# MLX90393_Magnetometer_Breakout.net
KiCad netlist of a schematic drawn in EAGLE
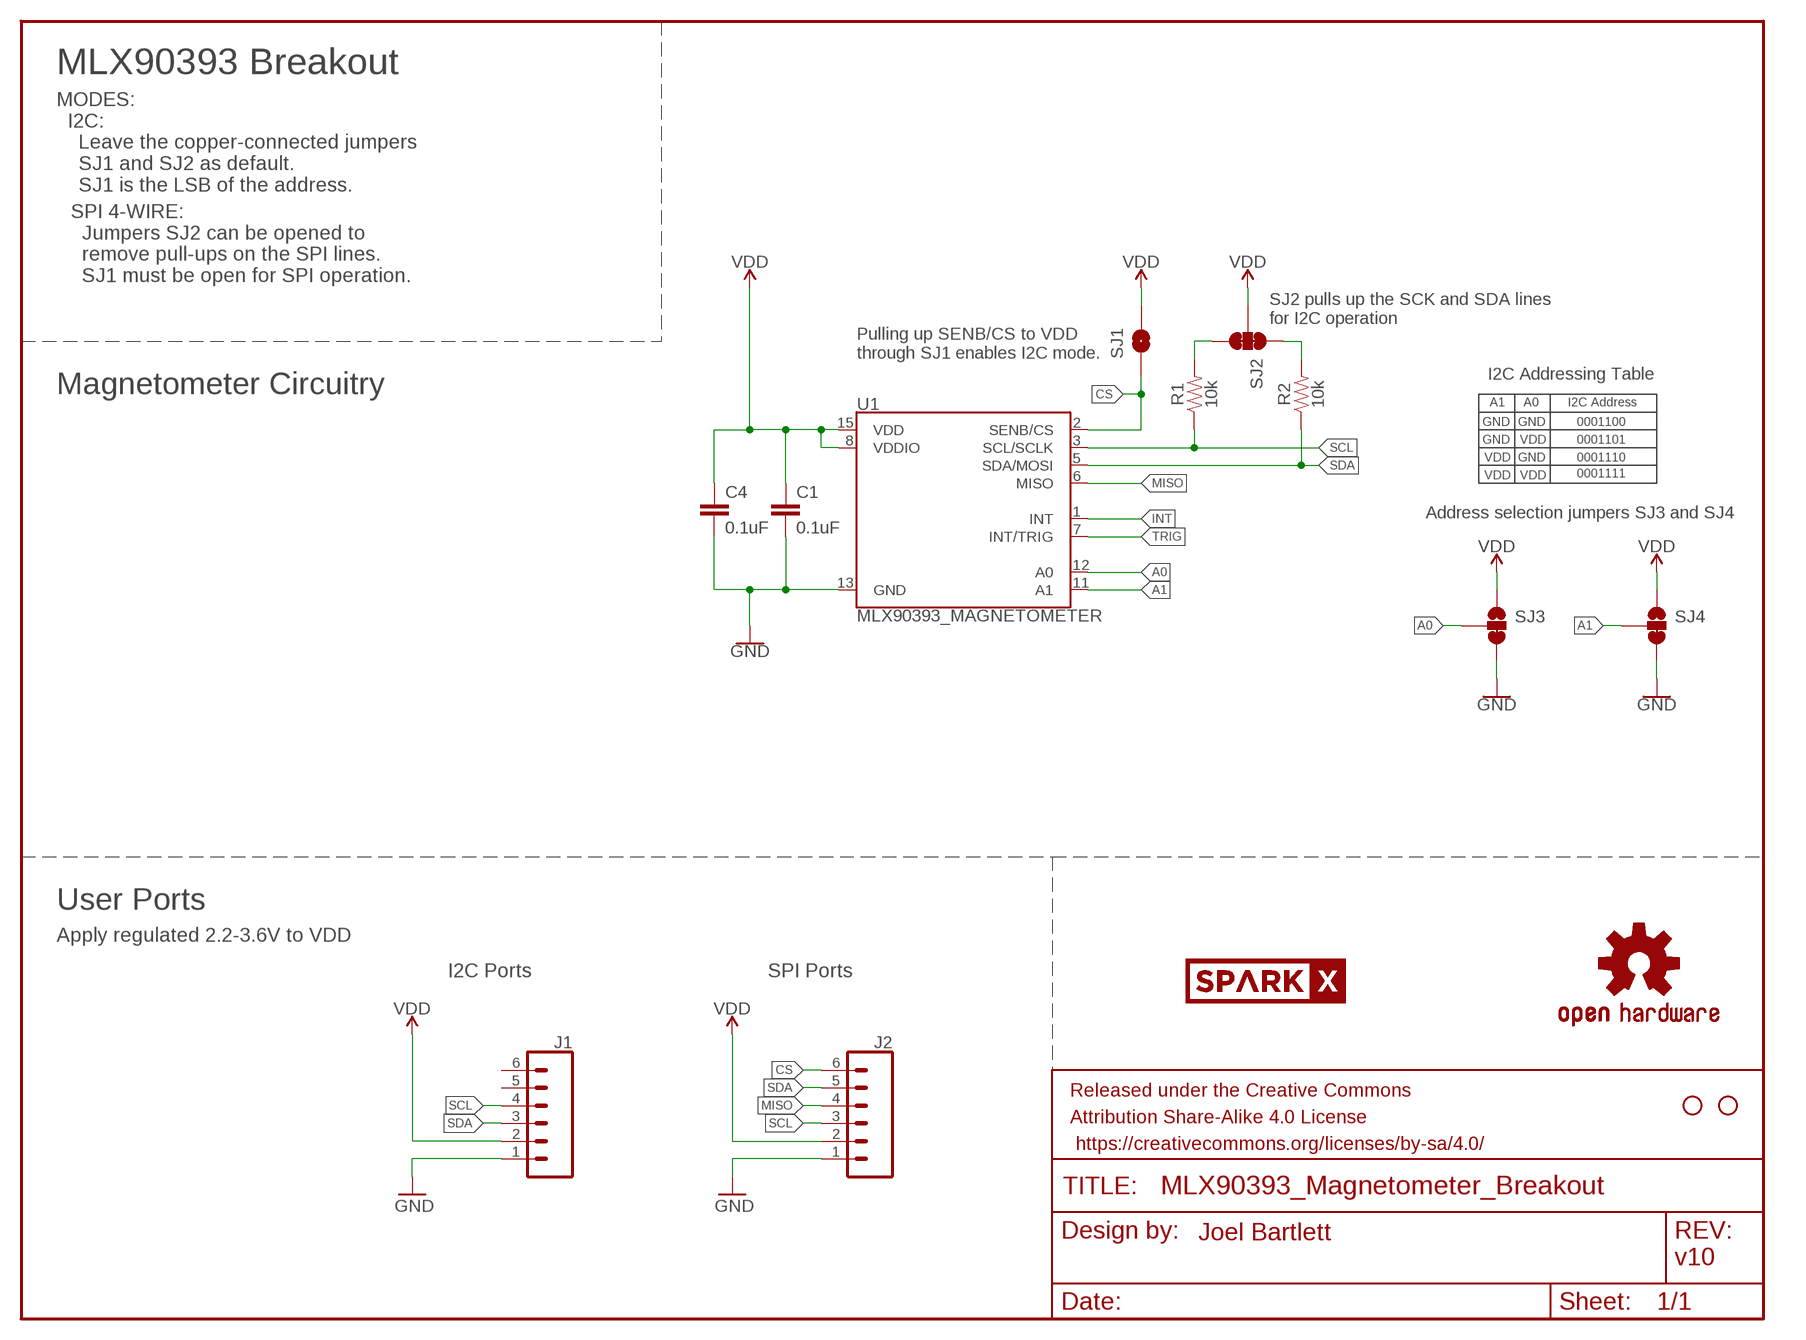
[diagram p0: schematic, sheet 1]

(export (version "E")
  (design (tool "Eeschema 10.0.6"))
  (components
    (comp (ref "C1")
      (value "0.1uF")
      (footprint "eagle-import:0603")
      (libsource (lib "eagle-import") (part "0.1UF-0603-25V-(+80/-20%)"))
    )
    (comp (ref "C4")
      (value "0.1uF")
      (footprint "eagle-import:0603")
      (libsource (lib "eagle-import") (part "0.1UF-0603-25V-(+80/-20%)"))
    )
    (comp (ref "FRAME2")
      (value "FRAME-LETTER")
      (footprint "eagle-import:CREATIVE_COMMONS")
      (libsource (lib "eagle-import") (part "FRAME-LETTER"))
    )
    (comp (ref "J1")
      (value "CONN_06NO_SILK_FEMALE_PTH")
      (footprint "eagle-import:1X06_NO_SILK")
      (libsource (lib "eagle-import") (part "CONN_06NO_SILK_FEMALE_PTH"))
    )
    (comp (ref "J2")
      (value "CONN_06NO_SILK_FEMALE_PTH")
      (footprint "eagle-import:1X06_NO_SILK")
      (libsource (lib "eagle-import") (part "CONN_06NO_SILK_FEMALE_PTH"))
    )
    (comp (ref "JP3")
      (value "STAND-OFF")
      (footprint "eagle-import:STAND-OFF")
      (libsource (lib "eagle-import") (part "STAND-OFF"))
    )
    (comp (ref "JP4")
      (value "STAND-OFF")
      (footprint "eagle-import:STAND-OFF")
      (libsource (lib "eagle-import") (part "STAND-OFF"))
    )
    (comp (ref "R1")
      (value "10k")
      (footprint "eagle-import:0603")
      (libsource (lib "eagle-import") (part "10KOHM-0603-1/10W-1%"))
    )
    (comp (ref "R2")
      (value "10k")
      (footprint "eagle-import:0603")
      (libsource (lib "eagle-import") (part "10KOHM-0603-1/10W-1%"))
    )
    (comp (ref "SJ1")
      (value "SOLDERJUMPERTRACE")
      (footprint "eagle-import:SJ_2S-TRACE")
      (libsource (lib "eagle-import") (part "SOLDERJUMPERTRACE"))
    )
    (comp (ref "SJ2")
      (value "JUMPER-PAD-3-NC_BY_TRACE")
      (footprint "eagle-import:PAD-JUMPER-3-3OF3_NC_BY_TRACE_YES_SILK_FULL_BOX")
      (libsource (lib "eagle-import") (part "JUMPER-PAD-3-NC_BY_TRACE"))
    )
    (comp (ref "SJ3")
      (value "JUMPER-SMT_3_1-NC_TRACE_SILK")
      (footprint "eagle-import:SMT-JUMPER_3_1-NC_TRACE_SILK")
      (libsource (lib "eagle-import") (part "JUMPER-SMT_3_1-NC_TRACE_SILK"))
    )
    (comp (ref "SJ4")
      (value "JUMPER-SMT_3_1-NC_TRACE_SILK")
      (footprint "eagle-import:SMT-JUMPER_3_1-NC_TRACE_SILK")
      (libsource (lib "eagle-import") (part "JUMPER-SMT_3_1-NC_TRACE_SILK"))
    )
    (comp (ref "U$1")
      (value "OSHW-LOGOS")
      (footprint "eagle-import:OSHW-LOGO-S")
      (libsource (lib "eagle-import") (part "OSHW-LOGOS"))
    )
    (comp (ref "U$2")
      (value "SPARKX-LOGO2")
      (footprint "eagle-import:SPARKX-TINY")
      (libsource (lib "eagle-import") (part "SPARKX-LOGO2"))
    )
    (comp (ref "U1")
      (value "MLX90393_MAGNETOMETER")
      (footprint "eagle-import:QFN-16")
      (libsource (lib "eagle-import") (part "MLX90393_MAGNETOMETER"))
    )
  )
  (nets
    (net (code "1") (name "A0") (class "Default")
      (node (ref "SJ3") (pin "2") (pinfunction "2_2") (pintype "passive"))
      (node (ref "U1") (pin "12") (pinfunction "A0_12") (pintype "bidirectional"))
    )
    (net (code "2") (name "A1") (class "Default")
      (node (ref "SJ4") (pin "2") (pinfunction "2_2") (pintype "passive"))
      (node (ref "U1") (pin "11") (pinfunction "A1_11") (pintype "bidirectional"))
    )
    (net (code "3") (name "CS") (class "Default")
      (node (ref "J2") (pin "6") (pinfunction "6_6") (pintype "passive"))
      (node (ref "SJ1") (pin "1") (pinfunction "1_1") (pintype "passive"))
      (node (ref "U1") (pin "2") (pinfunction "SENB/CS_2") (pintype "bidirectional"))
    )
    (net (code "4") (name "GND") (class "Default")
      (node (ref "C1") (pin "2") (pinfunction "2_2") (pintype "passive"))
      (node (ref "C4") (pin "2") (pinfunction "2_2") (pintype "passive"))
      (node (ref "J1") (pin "1") (pinfunction "1_1") (pintype "passive"))
      (node (ref "J2") (pin "1") (pinfunction "1_1") (pintype "passive"))
      (node (ref "SJ3") (pin "3") (pinfunction "3_3") (pintype "passive"))
      (node (ref "SJ4") (pin "3") (pinfunction "3_3") (pintype "passive"))
      (node (ref "U1") (pin "13") (pinfunction "GND_13") (pintype "bidirectional"))
    )
    (net (code "5") (name "INT") (class "Default")
      (node (ref "U1") (pin "1") (pinfunction "INT_1") (pintype "bidirectional"))
    )
    (net (code "6") (name "MISO") (class "Default")
      (node (ref "J2") (pin "4") (pinfunction "4_4") (pintype "passive"))
      (node (ref "U1") (pin "6") (pinfunction "MISO_6") (pintype "bidirectional"))
    )
    (net (code "7") (name "Net-(R1-Pad2)") (class "Default")
      (node (ref "R1") (pin "2") (pinfunction "2_2") (pintype "passive"))
      (node (ref "SJ2") (pin "3") (pinfunction "3_3") (pintype "passive"))
    )
    (net (code "8") (name "Net-(R2-Pad2)") (class "Default")
      (node (ref "R2") (pin "2") (pinfunction "2_2") (pintype "passive"))
      (node (ref "SJ2") (pin "1") (pinfunction "1_1") (pintype "passive"))
    )
    (net (code "9") (name "SCL") (class "Default")
      (node (ref "J1") (pin "4") (pinfunction "4_4") (pintype "passive"))
      (node (ref "J2") (pin "3") (pinfunction "3_3") (pintype "passive"))
      (node (ref "R1") (pin "1") (pinfunction "1_1") (pintype "passive"))
      (node (ref "U1") (pin "3") (pinfunction "SCL/SCLK_3") (pintype "bidirectional"))
    )
    (net (code "10") (name "SDA") (class "Default")
      (node (ref "J1") (pin "3") (pinfunction "3_3") (pintype "passive"))
      (node (ref "J2") (pin "5") (pinfunction "5_5") (pintype "passive"))
      (node (ref "R2") (pin "1") (pinfunction "1_1") (pintype "passive"))
      (node (ref "U1") (pin "5") (pinfunction "SDA/MOSI_5") (pintype "bidirectional"))
    )
    (net (code "11") (name "TRIG") (class "Default")
      (node (ref "U1") (pin "7") (pinfunction "INT/TRIG_7") (pintype "bidirectional"))
    )
    (net (code "12") (name "VDD") (class "Default")
      (node (ref "C1") (pin "1") (pinfunction "1_1") (pintype "passive"))
      (node (ref "C4") (pin "1") (pinfunction "1_1") (pintype "passive"))
      (node (ref "J1") (pin "2") (pinfunction "2_2") (pintype "passive"))
      (node (ref "J2") (pin "2") (pinfunction "2_2") (pintype "passive"))
      (node (ref "SJ1") (pin "2") (pinfunction "2_2") (pintype "passive"))
      (node (ref "SJ2") (pin "2") (pinfunction "2_2") (pintype "passive"))
      (node (ref "SJ3") (pin "1") (pinfunction "1_1") (pintype "passive"))
      (node (ref "SJ4") (pin "1") (pinfunction "1_1") (pintype "passive"))
      (node (ref "U1") (pin "15") (pinfunction "VDD_15") (pintype "bidirectional"))
      (node (ref "U1") (pin "8") (pinfunction "VDDIO_8") (pintype "bidirectional"))
    )
    (net (code "13") (name "unconnected-(J1-Pad5)") (class "Default")
      (node (ref "J1") (pin "5") (pinfunction "5_5") (pintype "passive"))
    )
    (net (code "14") (name "unconnected-(J1-Pad6)") (class "Default")
      (node (ref "J1") (pin "6") (pinfunction "6_6") (pintype "passive"))
    )
  )
)
